# ProDocument_CENTER_V1_2023-08-07.net
KiCad netlist of a schematic drawn in EasyEDA Pro
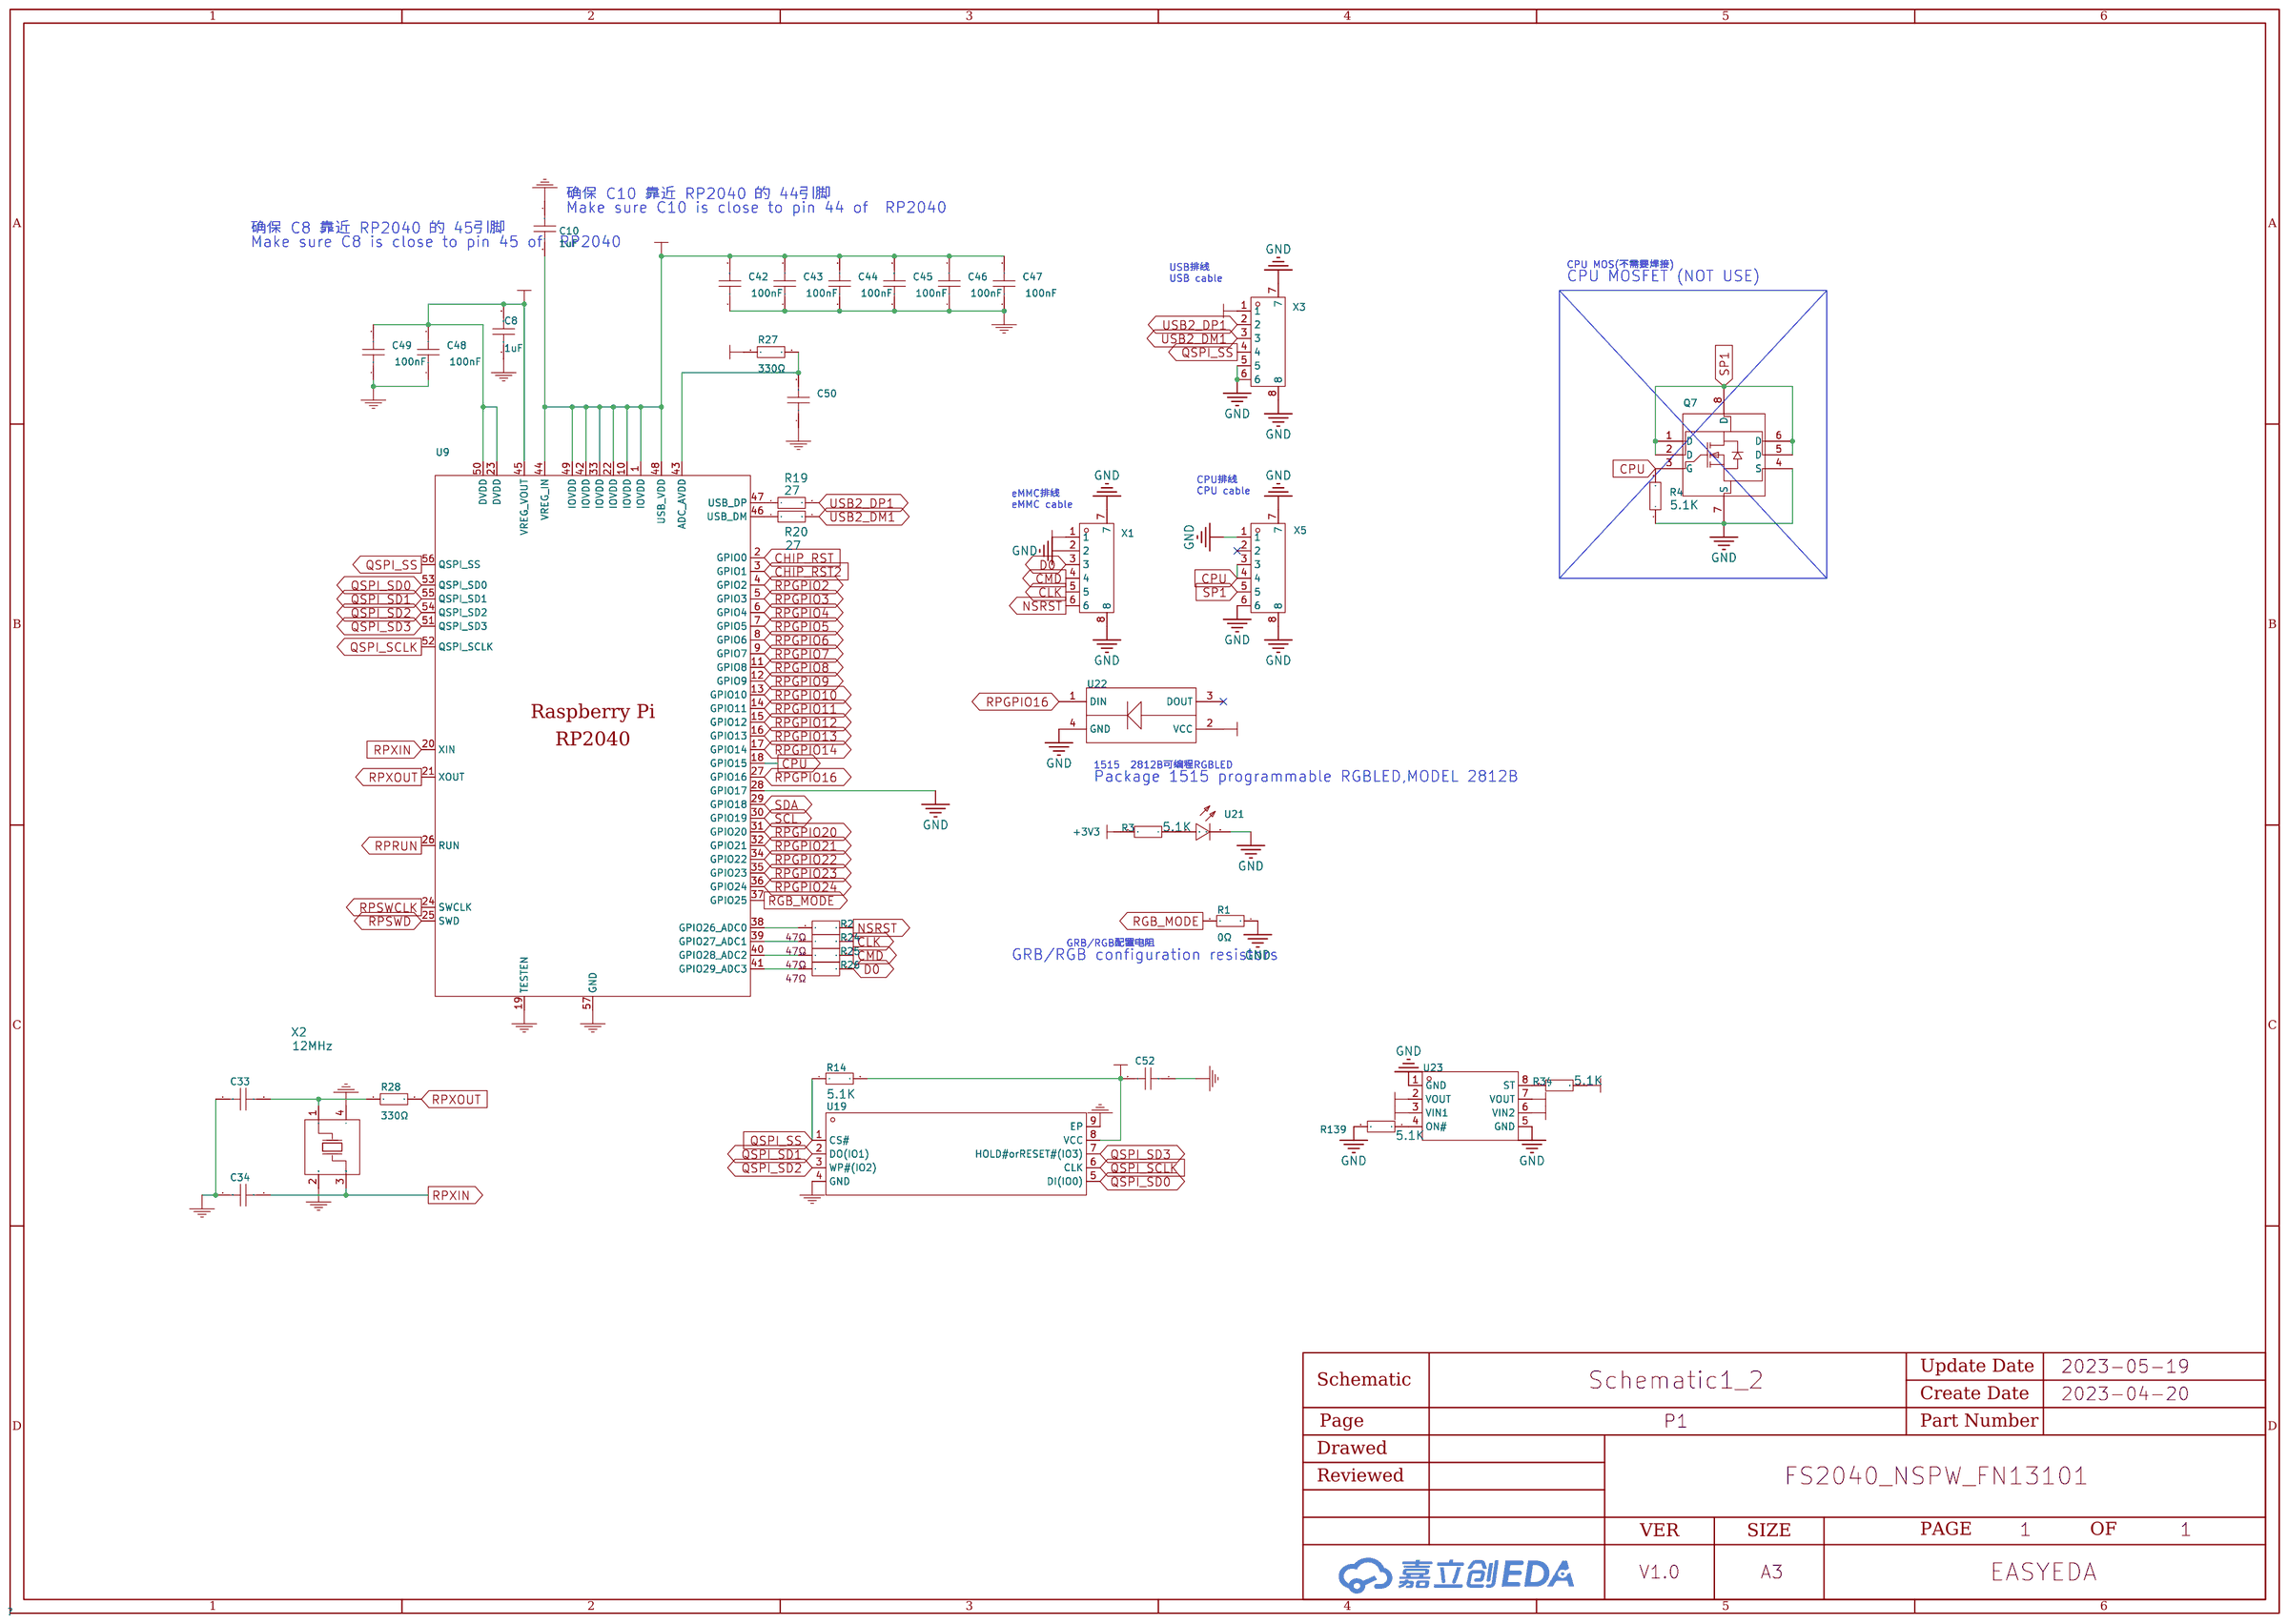
[diagram p0: schematic sheet]

(export (version "E")
  (design (tool "Eeschema 10.0.6"))
  (components
    (comp (ref "C8")
      (value "1uF")
      (footprint "easyedapro:C0402")
      (fields (field (name "Manufacturer Part") "GRM155B30J105KE18D") (field (name "Manufacturer") "MuRata"))
      (libsource (lib "easyedapro") (part "1uF"))
    )
    (comp (ref "C10")
      (value "1uF")
      (footprint "easyedapro:C0402")
      (fields (field (name "Manufacturer Part") "GRM155B30J105KE18D") (field (name "Manufacturer") "MuRata"))
      (libsource (lib "easyedapro") (part "1uF"))
    )
    (comp (ref "C33")
      (value "27pF")
      (footprint "easyedapro:C0402")
      (description "容值:27pF;精度:±5%;额定电压:50V;材质(温度系数):C0G;")
      (fields
        (field (name "Manufacturer Part") "CL05C270JB5NNNC")
        (field (name "Manufacturer") "SAMSUNG(三星)")
      )
      (libsource (lib "easyedapro") (part "CL05C270JB5NNNC"))
    )
    (comp (ref "C34")
      (value "27pF")
      (footprint "easyedapro:C0402")
      (description "容值:27pF;精度:±5%;额定电压:50V;材质(温度系数):C0G;")
      (fields
        (field (name "Manufacturer Part") "CL05C270JB5NNNC")
        (field (name "Manufacturer") "SAMSUNG(三星)")
      )
      (libsource (lib "easyedapro") (part "CL05C270JB5NNNC"))
    )
    (comp (ref "C42")
      (value "100nF")
      (footprint "easyedapro:C0402")
      (description "温度系数:X7R;额定电压:6.3V;容值:100nF;电容体长:-;精度:±10%;电容体宽:-;电容体厚度:-;")
      (fields
        (field (name "Manufacturer Part") "CC0402KRX7R5BB104")
        (field (name "Manufacturer") "YAGEO(国巨)")
      )
      (libsource (lib "easyedapro") (part "CC0402KRX7R5BB104"))
    )
    (comp (ref "C43")
      (value "100nF")
      (footprint "easyedapro:C0402")
      (description "温度系数:X7R;额定电压:6.3V;容值:100nF;电容体长:-;精度:±10%;电容体宽:-;电容体厚度:-;")
      (fields
        (field (name "Manufacturer Part") "CC0402KRX7R5BB104")
        (field (name "Manufacturer") "YAGEO(国巨)")
      )
      (libsource (lib "easyedapro") (part "CC0402KRX7R5BB104"))
    )
    (comp (ref "C44")
      (value "100nF")
      (footprint "easyedapro:C0402")
      (description "温度系数:X7R;额定电压:6.3V;容值:100nF;电容体长:-;精度:±10%;电容体宽:-;电容体厚度:-;")
      (fields
        (field (name "Manufacturer Part") "CC0402KRX7R5BB104")
        (field (name "Manufacturer") "YAGEO(国巨)")
      )
      (libsource (lib "easyedapro") (part "CC0402KRX7R5BB104"))
    )
    (comp (ref "C45")
      (value "100nF")
      (footprint "easyedapro:C0402")
      (description "温度系数:X7R;额定电压:6.3V;容值:100nF;电容体长:-;精度:±10%;电容体宽:-;电容体厚度:-;")
      (fields
        (field (name "Manufacturer Part") "CC0402KRX7R5BB104")
        (field (name "Manufacturer") "YAGEO(国巨)")
      )
      (libsource (lib "easyedapro") (part "CC0402KRX7R5BB104"))
    )
    (comp (ref "C46")
      (value "100nF")
      (footprint "easyedapro:C0402")
      (description "温度系数:X7R;额定电压:6.3V;容值:100nF;电容体长:-;精度:±10%;电容体宽:-;电容体厚度:-;")
      (fields
        (field (name "Manufacturer Part") "CC0402KRX7R5BB104")
        (field (name "Manufacturer") "YAGEO(国巨)")
      )
      (libsource (lib "easyedapro") (part "CC0402KRX7R5BB104"))
    )
    (comp (ref "C47")
      (value "100nF")
      (footprint "easyedapro:C0402")
      (description "温度系数:X7R;额定电压:6.3V;容值:100nF;电容体长:-;精度:±10%;电容体宽:-;电容体厚度:-;")
      (fields
        (field (name "Manufacturer Part") "CC0402KRX7R5BB104")
        (field (name "Manufacturer") "YAGEO(国巨)")
      )
      (libsource (lib "easyedapro") (part "CC0402KRX7R5BB104"))
    )
    (comp (ref "C48")
      (value "100nF")
      (footprint "easyedapro:C0402")
      (description "温度系数:X7R;额定电压:6.3V;容值:100nF;电容体长:-;精度:±10%;电容体宽:-;电容体厚度:-;")
      (fields
        (field (name "Manufacturer Part") "CC0402KRX7R5BB104")
        (field (name "Manufacturer") "YAGEO(国巨)")
      )
      (libsource (lib "easyedapro") (part "CC0402KRX7R5BB104"))
    )
    (comp (ref "C49")
      (value "100nF")
      (footprint "easyedapro:C0402")
      (description "温度系数:X7R;额定电压:6.3V;容值:100nF;电容体长:-;精度:±10%;电容体宽:-;电容体厚度:-;")
      (fields
        (field (name "Manufacturer Part") "CC0402KRX7R5BB104")
        (field (name "Manufacturer") "YAGEO(国巨)")
      )
      (libsource (lib "easyedapro") (part "CC0402KRX7R5BB104"))
    )
    (comp (ref "C50")
      (value "100nF")
      (footprint "easyedapro:C0402")
      (description "温度系数:X7R;额定电压:6.3V;容值:100nF;电容体长:-;精度:±10%;电容体宽:-;电容体厚度:-;")
      (fields
        (field (name "Manufacturer Part") "CC0402KRX7R5BB104")
        (field (name "Manufacturer") "YAGEO(国巨)")
      )
      (libsource (lib "easyedapro") (part "CC0402KRX7R5BB104"))
    )
    (comp (ref "C52")
      (value "100nF")
      (footprint "easyedapro:C0402")
      (description "温度系数:X7R;额定电压:6.3V;容值:100nF;电容体长:-;精度:±10%;电容体宽:-;电容体厚度:-;")
      (fields
        (field (name "Manufacturer Part") "CC0402KRX7R5BB104")
        (field (name "Manufacturer") "YAGEO(国巨)")
      )
      (libsource (lib "easyedapro") (part "CC0402KRX7R5BB104"))
    )
    (comp (ref "Q7")
      (value "IRFHS8342TRPBF")
      (footprint "easyedapro:PQFN-8_L2.0-W2.0-P0.65_IRFHS8342TRPBF")
      (fields (field (name "Manufacturer") "Infineon(英飞凌)"))
      (libsource (lib "easyedapro") (part "IRFHS8342TRPBF"))
    )
    (comp (ref "R1")
      (value "0Ω")
      (footprint "easyedapro:R0402")
      (description "电阻类型:厚膜电阻;阻值:0Ω;精度:±1%;功率:62.5mW;温度系数:±800ppm/°C;最大工作电压:50V;工作温度范围:-55°C~+155°C;")
      (fields
        (field (name "Manufacturer Part") "0402WGF0000TCE")
        (field (name "Manufacturer") "UNI-ROYAL(厚声)")
      )
      (libsource (lib "easyedapro") (part "0402WGF0000TCE"))
    )
    (comp (ref "R2")
      (value "ERJ2RKF47R0X")
      (footprint "easyedapro:R0402")
      (fields (field (name "Manufacturer") "PANASONIC(松下)") (field (name "LCSC Part Name") "47Ω"))
      (libsource (lib "easyedapro") (part "ERJ2RKF47R0X"))
    )
    (comp (ref "R3")
      (value "5.1K")
      (footprint "easyedapro:R0402_FS")
      (description "阻值:5.1kΩ;精度:±1%;功率:62.5mW;")
      (fields (field (name "Manufacturer Part") "RMC04025.1K1%N") (field (name "Manufacturer") "Tyohm(幸亚电阻)"))
      (libsource (lib "easyedapro") (part "RMC04025.1K1%N"))
    )
    (comp (ref "R4")
      (value "5.1K")
      (footprint "easyedapro:R0402_FS")
      (description "阻值:5.1kΩ;精度:±1%;功率:62.5mW;")
      (fields (field (name "Manufacturer Part") "RMC04025.1K1%N") (field (name "Manufacturer") "Tyohm(幸亚电阻)"))
      (libsource (lib "easyedapro") (part "RMC04025.1K1%N"))
    )
    (comp (ref "R14")
      (value "5.1K")
      (footprint "easyedapro:R0402_FS")
      (description "阻值:5.1kΩ;精度:±1%;功率:62.5mW;")
      (fields (field (name "Manufacturer Part") "RMC04025.1K1%N") (field (name "Manufacturer") "Tyohm(幸亚电阻)"))
      (libsource (lib "easyedapro") (part "RMC04025.1K1%N"))
    )
    (comp (ref "R19")
      (value "27")
      (footprint "easyedapro:R0402")
      (fields (field (name "Manufacturer Part") "0402WGF270JTCE") (field (name "Manufacturer") "UniOhm"))
      (libsource (lib "easyedapro") (part "27"))
    )
    (comp (ref "R20")
      (value "27")
      (footprint "easyedapro:R0402")
      (fields (field (name "Manufacturer Part") "0402WGF270JTCE") (field (name "Manufacturer") "UniOhm"))
      (libsource (lib "easyedapro") (part "27"))
    )
    (comp (ref "R24")
      (value "ERJ2RKF47R0X")
      (footprint "easyedapro:R0402")
      (fields (field (name "Manufacturer") "PANASONIC(松下)") (field (name "LCSC Part Name") "47Ω"))
      (libsource (lib "easyedapro") (part "ERJ2RKF47R0X"))
    )
    (comp (ref "R25")
      (value "ERJ2RKF47R0X")
      (footprint "easyedapro:R0402")
      (fields (field (name "Manufacturer") "PANASONIC(松下)") (field (name "LCSC Part Name") "47Ω"))
      (libsource (lib "easyedapro") (part "ERJ2RKF47R0X"))
    )
    (comp (ref "R26")
      (value "ERJ2RKF47R0X")
      (footprint "easyedapro:R0402")
      (fields (field (name "Manufacturer") "PANASONIC(松下)") (field (name "LCSC Part Name") "47Ω"))
      (libsource (lib "easyedapro") (part "ERJ2RKF47R0X"))
    )
    (comp (ref "R27")
      (value "330Ω")
      (footprint "easyedapro:R0402")
      (description "阻值:330Ω;精度:±1%;功率:1/16W;温度系数:±100ppm/°C;最大工作电压:50V;工作温度范围:-55°C~+155°C;")
      (fields
        (field (name "Manufacturer Part") "0402WGF3300TCE")
        (field (name "Manufacturer") "UNI-ROYAL(厚声)")
      )
      (libsource (lib "easyedapro") (part "0402WGF3300TCE"))
    )
    (comp (ref "R28")
      (value "330Ω")
      (footprint "easyedapro:R0402")
      (description "阻值:330Ω;精度:±1%;功率:1/16W;温度系数:±100ppm/°C;最大工作电压:50V;工作温度范围:-55°C~+155°C;")
      (fields
        (field (name "Manufacturer Part") "0402WGF3300TCE")
        (field (name "Manufacturer") "UNI-ROYAL(厚声)")
      )
      (libsource (lib "easyedapro") (part "0402WGF3300TCE"))
    )
    (comp (ref "R34")
      (value "5.1K")
      (footprint "easyedapro:R0402_FS")
      (description "阻值:5.1kΩ;精度:±1%;功率:62.5mW;")
      (fields (field (name "Manufacturer Part") "RMC04025.1K1%N") (field (name "Manufacturer") "Tyohm(幸亚电阻)"))
      (libsource (lib "easyedapro") (part "RMC04025.1K1%N"))
    )
    (comp (ref "R139")
      (value "5.1K")
      (footprint "easyedapro:R0402_FS")
      (description "阻值:5.1kΩ;精度:±1%;功率:62.5mW;")
      (fields (field (name "Manufacturer Part") "RMC04025.1K1%N") (field (name "Manufacturer") "Tyohm(幸亚电阻)"))
      (libsource (lib "easyedapro") (part "RMC04025.1K1%N"))
    )
    (comp (ref "U9")
      (value "~")
      (footprint "easyedapro:RPI_RP2040")
      (fields (field (name "Manufacturer Part") "RP2040") (field (name "Manufacturer") "Raspberry Pi(树莓派)"))
      (libsource (lib "easyedapro") (part "RPI_RP2040"))
    )
    (comp (ref "U19")
      (value "W25Q16JVUXIQ")
      (footprint "easyedapro:USON-8_L3.0-W2.0-P0.50-BL-EP")
      (fields (field (name "Manufacturer") "WINBOND(华邦)"))
      (libsource (lib "easyedapro") (part "W25Q16JVUXIQ"))
    )
    (comp (ref "U21")
      (value "~")
      (footprint "easyedapro:LED 0603_RED")
      (libsource (lib "easyedapro") (part "0603LED"))
    )
    (comp (ref "U22")
      (value "~")
      (footprint "easyedapro:1515RGB")
      (libsource (lib "easyedapro") (part "1515RGB"))
    )
    (comp (ref "U23")
      (value "LM66200DRLR")
      (footprint "easyedapro:SOT-583-8_L2.1-W1.2-P0.50-LS1.6-BL")
      (fields (field (name "Manufacturer") "TI(德州仪器)"))
      (libsource (lib "easyedapro") (part "LM66200DRLR"))
    )
    (comp (ref "X1")
      (value "FH34SRJ-6S-0.5SH(50)")
      (fields (field (name "Manufacturer") "HRS(广濑)"))
      (libsource (lib "easyedapro") (part "AFC48-S06FKA-HF"))
    )
    (comp (ref "X2")
      (value "12MHz")
      (footprint "easyedapro:OSC-SMD_4P-L3.2-W2.5-BL")
      (fields (field (name "Manufacturer") "Zhejiang Abel Elec"))
      (libsource (lib "easyedapro") (part "12MHz"))
    )
    (comp (ref "X3")
      (value "FH34SRJ-6S-0.5SH(50)")
      (fields (field (name "Manufacturer") "HRS(广濑)"))
      (libsource (lib "easyedapro") (part "AFC48-S06FKA-HF"))
    )
    (comp (ref "X5")
      (value "FH34SRJ-6S-0.5SH(50)")
      (fields (field (name "Manufacturer") "HRS(广濑)"))
      (libsource (lib "easyedapro") (part "AFC48-S06FKA-HF"))
    )
  )
  (nets
    (net (code "1") (name "+1V1") (class "Default")
      (node (ref "C48") (pin "2") (pinfunction "2_2") (pintype "input"))
      (node (ref "C49") (pin "2") (pinfunction "2_2") (pintype "input"))
      (node (ref "C8") (pin "2") (pinfunction "2_2") (pintype "input"))
      (node (ref "U9") (pin "23") (pinfunction "DVDD_23") (pintype "bidirectional"))
      (node (ref "U9") (pin "45") (pinfunction "VREG_VOUT_45") (pintype "bidirectional"))
      (node (ref "U9") (pin "50") (pinfunction "DVDD_50") (pintype "bidirectional"))
    )
    (net (code "2") (name "+3V3") (class "Default")
      (node (ref "C10") (pin "2") (pinfunction "2_2") (pintype "input"))
      (node (ref "C42") (pin "2") (pinfunction "2_2") (pintype "input"))
      (node (ref "C43") (pin "2") (pinfunction "2_2") (pintype "input"))
      (node (ref "C44") (pin "2") (pinfunction "2_2") (pintype "input"))
      (node (ref "C45") (pin "2") (pinfunction "2_2") (pintype "input"))
      (node (ref "C46") (pin "2") (pinfunction "2_2") (pintype "input"))
      (node (ref "C47") (pin "2") (pinfunction "2_2") (pintype "input"))
      (node (ref "C52") (pin "2") (pinfunction "2_2") (pintype "input"))
      (node (ref "R14") (pin "2") (pinfunction "2_2") (pintype "input"))
      (node (ref "R27") (pin "1") (pinfunction "1_1") (pintype "input"))
      (node (ref "R3") (pin "2") (pinfunction "2_2") (pintype "input"))
      (node (ref "U19") (pin "8") (pinfunction "VCC_8") (pintype "input"))
      (node (ref "U22") (pin "2") (pinfunction "VCC_2") (pintype "input"))
      (node (ref "U23") (pin "2") (pinfunction "VOUT_2") (pintype "input"))
      (node (ref "U23") (pin "7") (pinfunction "VOUT_7") (pintype "input"))
      (node (ref "U9") (pin "1") (pinfunction "IOVDD_1") (pintype "bidirectional"))
      (node (ref "U9") (pin "10") (pinfunction "IOVDD_10") (pintype "bidirectional"))
      (node (ref "U9") (pin "22") (pinfunction "IOVDD_22") (pintype "bidirectional"))
      (node (ref "U9") (pin "33") (pinfunction "IOVDD_33") (pintype "bidirectional"))
      (node (ref "U9") (pin "42") (pinfunction "IOVDD_42") (pintype "bidirectional"))
      (node (ref "U9") (pin "44") (pinfunction "VREG_IN_44") (pintype "bidirectional"))
      (node (ref "U9") (pin "48") (pinfunction "USB_VDD_48") (pintype "bidirectional"))
      (node (ref "U9") (pin "49") (pinfunction "IOVDD_49") (pintype "bidirectional"))
    )
    (net (code "3") (name "+3V3EMMC") (class "Default")
      (node (ref "R34") (pin "1") (pinfunction "1_1") (pintype "input"))
      (node (ref "U23") (pin "3") (pinfunction "VIN1_3") (pintype "input"))
      (node (ref "X1") (pin "1") (pinfunction "1_1") (pintype "input"))
    )
    (net (code "4") (name "+3V3INUSB") (class "Default")
      (node (ref "U23") (pin "6") (pinfunction "VIN2_6") (pintype "input"))
      (node (ref "X3") (pin "1") (pinfunction "1_1") (pintype "input"))
    )
    (net (code "5") (name "CHIP_RST") (class "Default")
      (node (ref "U9") (pin "2") (pinfunction "GPIO0_2") (pintype "bidirectional"))
    )
    (net (code "6") (name "CHIP_RST2") (class "Default")
      (node (ref "U9") (pin "3") (pinfunction "GPIO1_3") (pintype "bidirectional"))
    )
    (net (code "7") (name "CLK") (class "Default")
      (node (ref "R24") (pin "2") (pinfunction "2_2") (pintype "input"))
      (node (ref "X1") (pin "5") (pinfunction "5_5") (pintype "input"))
    )
    (net (code "8") (name "CMD") (class "Default")
      (node (ref "R25") (pin "2") (pinfunction "2_2") (pintype "input"))
      (node (ref "X1") (pin "4") (pinfunction "4_4") (pintype "input"))
    )
    (net (code "9") (name "CPU") (class "Default")
      (node (ref "Q7") (pin "3") (pinfunction "G_3") (pintype "input"))
      (node (ref "R4") (pin "2") (pinfunction "2_2") (pintype "input"))
      (node (ref "U9") (pin "18") (pinfunction "GPIO15_18") (pintype "bidirectional"))
      (node (ref "X5") (pin "3") (pinfunction "3_3") (pintype "input"))
      (node (ref "X5") (pin "4") (pinfunction "4_4") (pintype "input"))
    )
    (net (code "10") (name "D0") (class "Default")
      (node (ref "R26") (pin "2") (pinfunction "2_2") (pintype "input"))
      (node (ref "X1") (pin "3") (pinfunction "3_3") (pintype "input"))
    )
    (net (code "11") (name "GND") (class "Default")
      (node (ref "C10") (pin "1") (pinfunction "1_1") (pintype "input"))
      (node (ref "C33") (pin "2") (pinfunction "2_2") (pintype "input"))
      (node (ref "C34") (pin "2") (pinfunction "2_2") (pintype "input"))
      (node (ref "C42") (pin "1") (pinfunction "1_1") (pintype "input"))
      (node (ref "C43") (pin "1") (pinfunction "1_1") (pintype "input"))
      (node (ref "C44") (pin "1") (pinfunction "1_1") (pintype "input"))
      (node (ref "C45") (pin "1") (pinfunction "1_1") (pintype "input"))
      (node (ref "C46") (pin "1") (pinfunction "1_1") (pintype "input"))
      (node (ref "C47") (pin "1") (pinfunction "1_1") (pintype "input"))
      (node (ref "C48") (pin "1") (pinfunction "1_1") (pintype "input"))
      (node (ref "C49") (pin "1") (pinfunction "1_1") (pintype "input"))
      (node (ref "C50") (pin "1") (pinfunction "1_1") (pintype "input"))
      (node (ref "C52") (pin "1") (pinfunction "1_1") (pintype "input"))
      (node (ref "C8") (pin "1") (pinfunction "1_1") (pintype "input"))
      (node (ref "Q7") (pin "4") (pinfunction "S_4") (pintype "input"))
      (node (ref "Q7") (pin "7") (pinfunction "S_7") (pintype "input"))
      (node (ref "R1") (pin "1") (pinfunction "1_1") (pintype "input"))
      (node (ref "R139") (pin "2") (pinfunction "2_2") (pintype "input"))
      (node (ref "R4") (pin "1") (pinfunction "1_1") (pintype "input"))
      (node (ref "U19") (pin "4") (pinfunction "GND_4") (pintype "input"))
      (node (ref "U19") (pin "9") (pinfunction "EP_9") (pintype "input"))
      (node (ref "U21") (pin "2") (pinfunction "C_2") (pintype "input"))
      (node (ref "U22") (pin "4") (pinfunction "GND_4") (pintype "input"))
      (node (ref "U23") (pin "1") (pinfunction "GND_1") (pintype "input"))
      (node (ref "U23") (pin "5") (pinfunction "GND_5") (pintype "input"))
      (node (ref "U9") (pin "19") (pinfunction "TESTEN_19") (pintype "input"))
      (node (ref "U9") (pin "28") (pinfunction "GPIO17_28") (pintype "bidirectional"))
      (node (ref "U9") (pin "57") (pinfunction "GND_57") (pintype "bidirectional"))
      (node (ref "X1") (pin "2") (pinfunction "2_2") (pintype "input"))
      (node (ref "X1") (pin "7") (pinfunction "7_7") (pintype "input"))
      (node (ref "X1") (pin "8") (pinfunction "8_8") (pintype "input"))
      (node (ref "X2") (pin "2") (pinfunction "2_2") (pintype "input"))
      (node (ref "X2") (pin "4") (pinfunction "4_4") (pintype "input"))
      (node (ref "X3") (pin "5") (pinfunction "5_5") (pintype "input"))
      (node (ref "X3") (pin "6") (pinfunction "6_6") (pintype "input"))
      (node (ref "X3") (pin "7") (pinfunction "7_7") (pintype "input"))
      (node (ref "X3") (pin "8") (pinfunction "8_8") (pintype "input"))
      (node (ref "X5") (pin "1") (pinfunction "1_1") (pintype "input"))
      (node (ref "X5") (pin "6") (pinfunction "6_6") (pintype "input"))
      (node (ref "X5") (pin "7") (pinfunction "7_7") (pintype "input"))
      (node (ref "X5") (pin "8") (pinfunction "8_8") (pintype "input"))
    )
    (net (code "12") (name "NSRST") (class "Default")
      (node (ref "R2") (pin "2") (pinfunction "2_2") (pintype "input"))
      (node (ref "X1") (pin "6") (pinfunction "6_6") (pintype "input"))
    )
    (net (code "13") (name "Net-(U9-ADC_AVDD)") (class "Default")
      (node (ref "C50") (pin "2") (pinfunction "2_2") (pintype "input"))
      (node (ref "R27") (pin "2") (pinfunction "2_2") (pintype "input"))
      (node (ref "U9") (pin "43") (pinfunction "ADC_AVDD_43") (pintype "bidirectional"))
    )
    (net (code "14") (name "Net-(U9-GPIO26_ADC0)") (class "Default")
      (node (ref "R2") (pin "1") (pinfunction "1_1") (pintype "input"))
      (node (ref "U9") (pin "38") (pinfunction "GPIO26_ADC0_38") (pintype "bidirectional"))
    )
    (net (code "15") (name "Net-(U9-GPIO27_ADC1)") (class "Default")
      (node (ref "R24") (pin "1") (pinfunction "1_1") (pintype "input"))
      (node (ref "U9") (pin "39") (pinfunction "GPIO27_ADC1_39") (pintype "bidirectional"))
    )
    (net (code "16") (name "Net-(U9-GPIO28_ADC2)") (class "Default")
      (node (ref "R25") (pin "1") (pinfunction "1_1") (pintype "input"))
      (node (ref "U9") (pin "40") (pinfunction "GPIO28_ADC2_40") (pintype "bidirectional"))
    )
    (net (code "17") (name "Net-(U9-GPIO29_ADC3)") (class "Default")
      (node (ref "R26") (pin "1") (pinfunction "1_1") (pintype "input"))
      (node (ref "U9") (pin "41") (pinfunction "GPIO29_ADC3_41") (pintype "bidirectional"))
    )
    (net (code "18") (name "Net-(U9-USB_DM)") (class "Default")
      (node (ref "R20") (pin "1") (pinfunction "1_1") (pintype "input"))
      (node (ref "U9") (pin "46") (pinfunction "USB_DM_46") (pintype "bidirectional"))
    )
    (net (code "19") (name "Net-(U9-USB_DP)") (class "Default")
      (node (ref "R19") (pin "1") (pinfunction "1_1") (pintype "input"))
      (node (ref "U9") (pin "47") (pinfunction "USB_DP_47") (pintype "bidirectional"))
    )
    (net (code "20") (name "Net-(U21-A)") (class "Default")
      (node (ref "R3") (pin "1") (pinfunction "1_1") (pintype "input"))
      (node (ref "U21") (pin "1") (pinfunction "A_1") (pintype "input"))
    )
    (net (code "21") (name "Net-(U23-ON#)") (class "Default")
      (node (ref "R139") (pin "1") (pinfunction "1_1") (pintype "input"))
      (node (ref "U23") (pin "4") (pinfunction "ON#_4") (pintype "input"))
    )
    (net (code "22") (name "Net-(U23-ST)") (class "Default")
      (node (ref "R34") (pin "2") (pinfunction "2_2") (pintype "input"))
      (node (ref "U23") (pin "8") (pinfunction "ST_8") (pintype "input"))
    )
    (net (code "23") (name "Net-(X2-OSC1)") (class "Default")
      (node (ref "C33") (pin "1") (pinfunction "1_1") (pintype "input"))
      (node (ref "R28") (pin "2") (pinfunction "2_2") (pintype "input"))
      (node (ref "X2") (pin "1") (pinfunction "OSC1_1") (pintype "input"))
    )
    (net (code "24") (name "QSPI_SCLK") (class "Default")
      (node (ref "U19") (pin "6") (pinfunction "CLK_6") (pintype "input"))
      (node (ref "U9") (pin "52") (pinfunction "QSPI_SCLK_52") (pintype "output"))
    )
    (net (code "25") (name "QSPI_SD0") (class "Default")
      (node (ref "U19") (pin "5") (pinfunction "DI(IO0)_5") (pintype "input"))
      (node (ref "U9") (pin "53") (pinfunction "QSPI_SD0_53") (pintype "bidirectional"))
    )
    (net (code "26") (name "QSPI_SD1") (class "Default")
      (node (ref "U19") (pin "2") (pinfunction "DO(IO1)_2") (pintype "input"))
      (node (ref "U9") (pin "55") (pinfunction "QSPI_SD1_55") (pintype "bidirectional"))
    )
    (net (code "27") (name "QSPI_SD2") (class "Default")
      (node (ref "U19") (pin "3") (pinfunction "WP#(IO2)_3") (pintype "input"))
      (node (ref "U9") (pin "54") (pinfunction "QSPI_SD2_54") (pintype "bidirectional"))
    )
    (net (code "28") (name "QSPI_SD3") (class "Default")
      (node (ref "U19") (pin "7") (pinfunction "HOLD#orRESET#(IO3)_7") (pintype "input"))
      (node (ref "U9") (pin "51") (pinfunction "QSPI_SD3_51") (pintype "bidirectional"))
    )
    (net (code "29") (name "QSPI_SS") (class "Default")
      (node (ref "R14") (pin "1") (pinfunction "1_1") (pintype "input"))
      (node (ref "U19") (pin "1") (pinfunction "CS#_1") (pintype "input"))
      (node (ref "U9") (pin "56") (pinfunction "QSPI_SS_56") (pintype "bidirectional"))
      (node (ref "X3") (pin "4") (pinfunction "4_4") (pintype "input"))
    )
    (net (code "30") (name "RGB_MODE") (class "Default")
      (node (ref "R1") (pin "2") (pinfunction "2_2") (pintype "input"))
      (node (ref "U9") (pin "37") (pinfunction "GPIO25_37") (pintype "bidirectional"))
    )
    (net (code "31") (name "RPGPIO2") (class "Default")
      (node (ref "U9") (pin "4") (pinfunction "GPIO2_4") (pintype "bidirectional"))
    )
    (net (code "32") (name "RPGPIO3") (class "Default")
      (node (ref "U9") (pin "5") (pinfunction "GPIO3_5") (pintype "bidirectional"))
    )
    (net (code "33") (name "RPGPIO4") (class "Default")
      (node (ref "U9") (pin "6") (pinfunction "GPIO4_6") (pintype "bidirectional"))
    )
    (net (code "34") (name "RPGPIO5") (class "Default")
      (node (ref "U9") (pin "7") (pinfunction "GPIO5_7") (pintype "bidirectional"))
    )
    (net (code "35") (name "RPGPIO6") (class "Default")
      (node (ref "U9") (pin "8") (pinfunction "GPIO6_8") (pintype "bidirectional"))
    )
    (net (code "36") (name "RPGPIO7") (class "Default")
      (node (ref "U9") (pin "9") (pinfunction "GPIO7_9") (pintype "bidirectional"))
    )
    (net (code "37") (name "RPGPIO8") (class "Default")
      (node (ref "U9") (pin "11") (pinfunction "GPIO8_11") (pintype "bidirectional"))
    )
    (net (code "38") (name "RPGPIO9") (class "Default")
      (node (ref "U9") (pin "12") (pinfunction "GPIO9_12") (pintype "bidirectional"))
    )
    (net (code "39") (name "RPGPIO10") (class "Default")
      (node (ref "U9") (pin "13") (pinfunction "GPIO10_13") (pintype "bidirectional"))
    )
    (net (code "40") (name "RPGPIO11") (class "Default")
      (node (ref "U9") (pin "14") (pinfunction "GPIO11_14") (pintype "bidirectional"))
    )
    (net (code "41") (name "RPGPIO12") (class "Default")
      (node (ref "U9") (pin "15") (pinfunction "GPIO12_15") (pintype "bidirectional"))
    )
    (net (code "42") (name "RPGPIO13") (class "Default")
      (node (ref "U9") (pin "16") (pinfunction "GPIO13_16") (pintype "bidirectional"))
    )
    (net (code "43") (name "RPGPIO14") (class "Default")
      (node (ref "U9") (pin "17") (pinfunction "GPIO14_17") (pintype "bidirectional"))
    )
    (net (code "44") (name "RPGPIO16") (class "Default")
      (node (ref "U22") (pin "1") (pinfunction "DIN_1") (pintype "input"))
      (node (ref "U9") (pin "27") (pinfunction "GPIO16_27") (pintype "bidirectional"))
    )
    (net (code "45") (name "RPGPIO20") (class "Default")
      (node (ref "U9") (pin "31") (pinfunction "GPIO20_31") (pintype "bidirectional"))
    )
    (net (code "46") (name "RPGPIO21") (class "Default")
      (node (ref "U9") (pin "32") (pinfunction "GPIO21_32") (pintype "bidirectional"))
    )
    (net (code "47") (name "RPGPIO22") (class "Default")
      (node (ref "U9") (pin "34") (pinfunction "GPIO22_34") (pintype "bidirectional"))
    )
    (net (code "48") (name "RPGPIO23") (class "Default")
      (node (ref "U9") (pin "35") (pinfunction "GPIO23_35") (pintype "bidirectional"))
    )
    (net (code "49") (name "RPGPIO24") (class "Default")
      (node (ref "U9") (pin "36") (pinfunction "GPIO24_36") (pintype "bidirectional"))
    )
    (net (code "50") (name "RPRUN") (class "Default")
      (node (ref "U9") (pin "26") (pinfunction "RUN_26") (pintype "input"))
    )
    (net (code "51") (name "RPSWCLK") (class "Default")
      (node (ref "U9") (pin "24") (pinfunction "SWCLK_24") (pintype "output"))
    )
    (net (code "52") (name "RPSWD") (class "Default")
      (node (ref "U9") (pin "25") (pinfunction "SWD_25") (pintype "bidirectional"))
    )
    (net (code "53") (name "RPXIN") (class "Default")
      (node (ref "C34") (pin "1") (pinfunction "1_1") (pintype "input"))
      (node (ref "U9") (pin "20") (pinfunction "XIN_20") (pintype "input"))
      (node (ref "X2") (pin "3") (pinfunction "OSC2_3") (pintype "input"))
    )
    (net (code "54") (name "RPXOUT") (class "Default")
      (node (ref "R28") (pin "1") (pinfunction "1_1") (pintype "input"))
      (node (ref "U9") (pin "21") (pinfunction "XOUT_21") (pintype "input"))
    )
    (net (code "55") (name "SCL") (class "Default")
      (node (ref "U9") (pin "30") (pinfunction "GPIO19_30") (pintype "bidirectional"))
    )
    (net (code "56") (name "SDA") (class "Default")
      (node (ref "U9") (pin "29") (pinfunction "GPIO18_29") (pintype "bidirectional"))
    )
    (net (code "57") (name "SP1") (class "Default")
      (node (ref "Q7") (pin "1") (pinfunction "D_1") (pintype "input"))
      (node (ref "Q7") (pin "2") (pinfunction "D_2") (pintype "input"))
      (node (ref "Q7") (pin "5") (pinfunction "D_5") (pintype "input"))
      (node (ref "Q7") (pin "6") (pinfunction "D_6") (pintype "input"))
      (node (ref "Q7") (pin "8") (pinfunction "D_8") (pintype "input"))
      (node (ref "X5") (pin "5") (pinfunction "5_5") (pintype "input"))
    )
    (net (code "58") (name "USB2_DM1") (class "Default")
      (node (ref "R20") (pin "2") (pinfunction "2_2") (pintype "input"))
      (node (ref "X3") (pin "3") (pinfunction "3_3") (pintype "input"))
    )
    (net (code "59") (name "USB2_DP1") (class "Default")
      (node (ref "R19") (pin "2") (pinfunction "2_2") (pintype "input"))
      (node (ref "X3") (pin "2") (pinfunction "2_2") (pintype "input"))
    )
    (net (code "60") (name "unconnected-(U22-DOUT-Pad3)") (class "Default")
      (node (ref "U22") (pin "3") (pinfunction "DOUT_3") (pintype "input+no_connect"))
    )
    (net (code "61") (name "unconnected-(X5-Pad2)") (class "Default")
      (node (ref "X5") (pin "2") (pinfunction "2_2") (pintype "input+no_connect"))
    )
  )
)
